# ardBeeQueenWMountHoles50x52.net
KiCad netlist of a schematic drawn in EAGLE
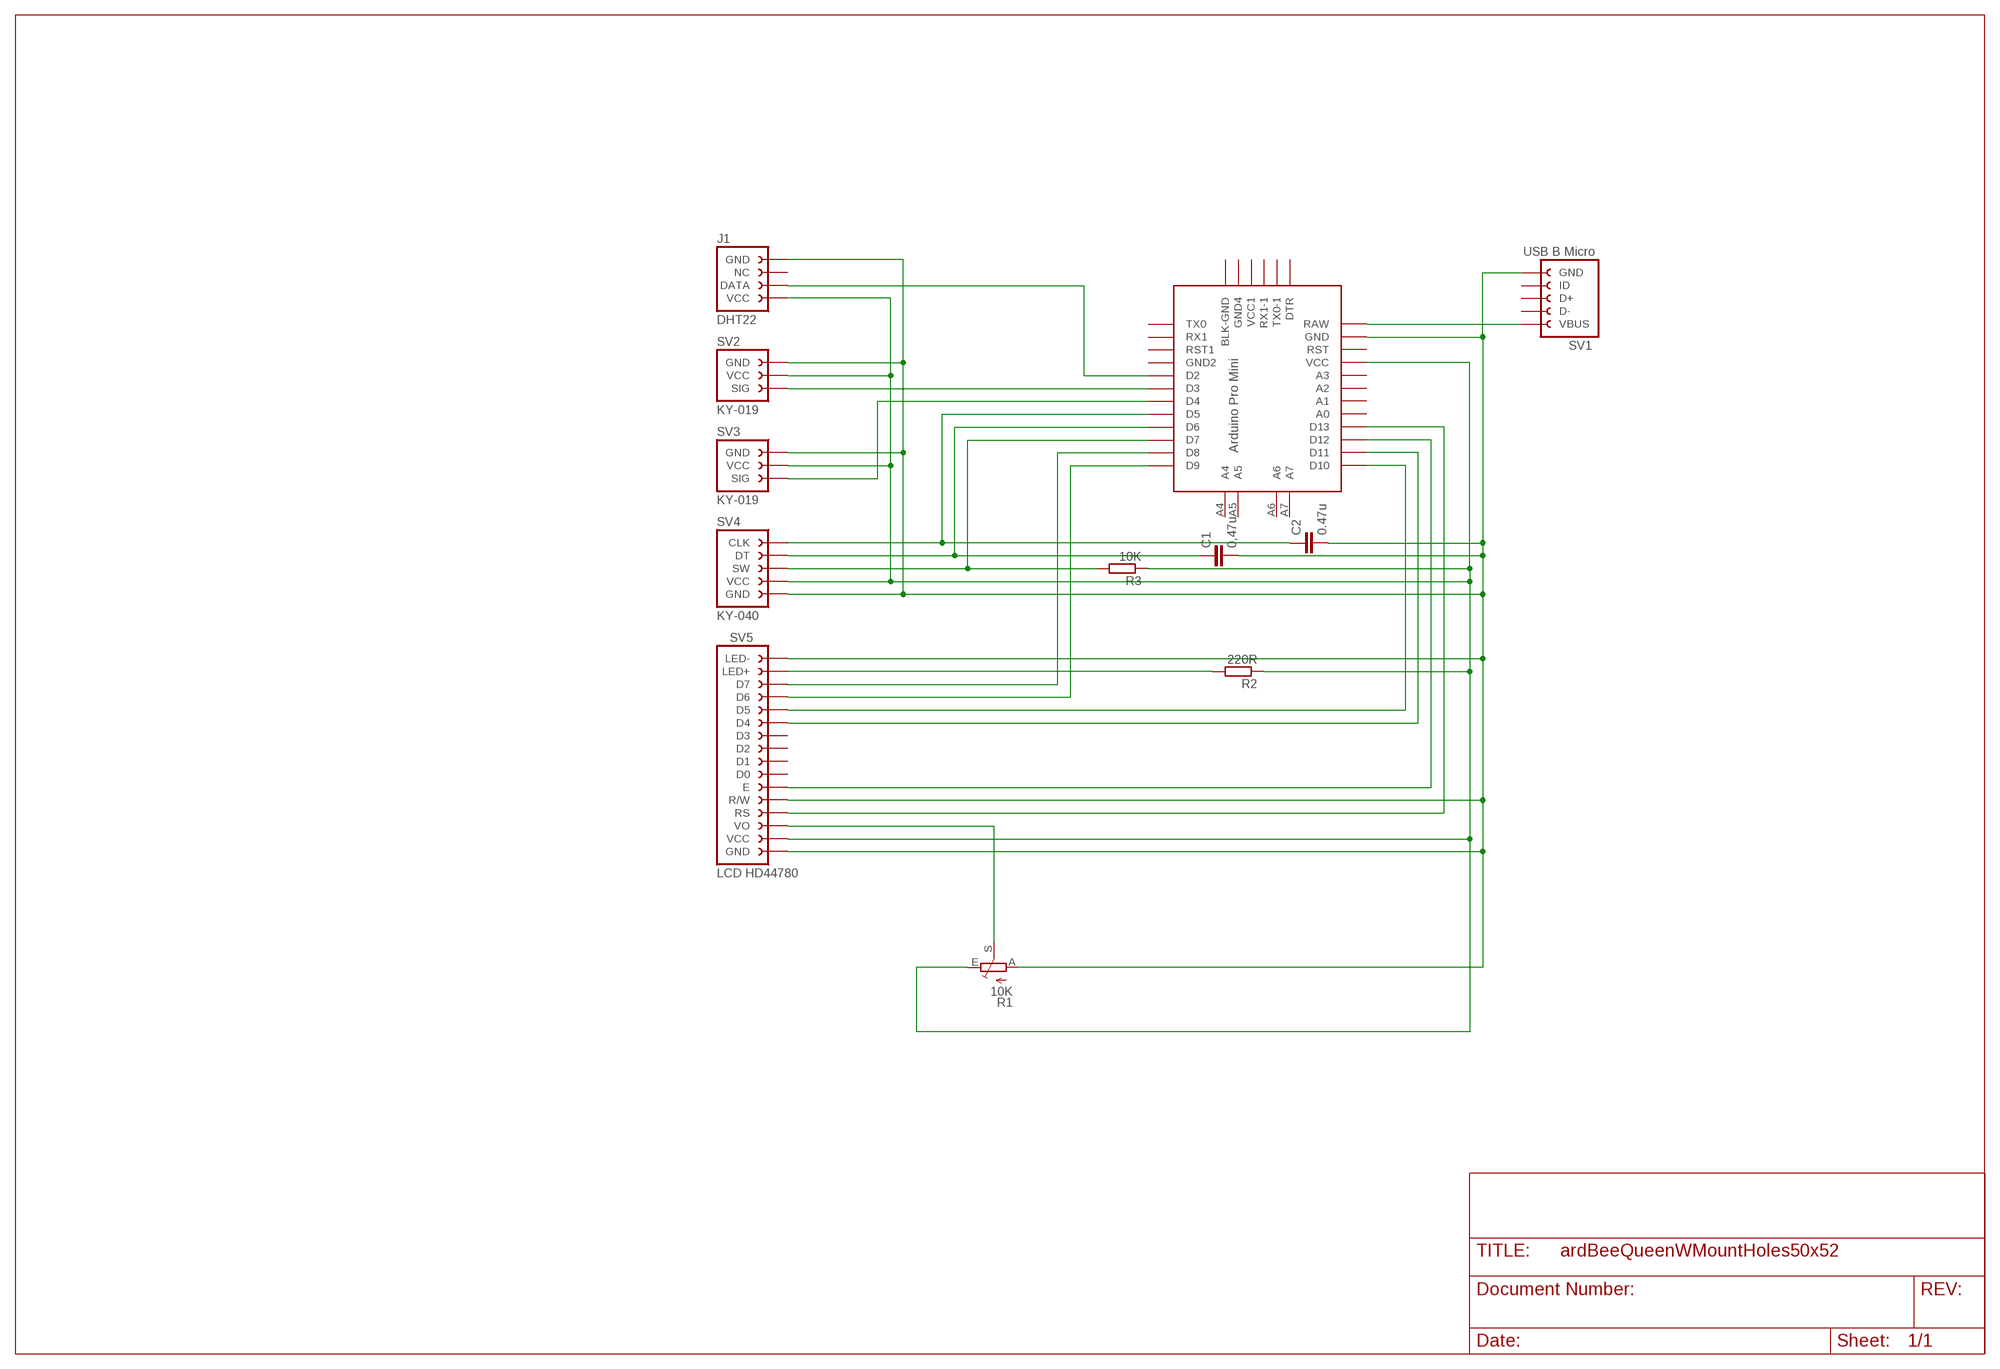
[diagram p0: schematic, sheet 1]

(export (version "E")
  (design (tool "Eeschema 10.0.6"))
  (components
    (comp (ref "C1")
      (value "0,47u")
      (footprint "eagle-import:C050-024X044")
      (libsource (lib "eagle-import") (part "C-EU050-024X044"))
    )
    (comp (ref "C2")
      (value "0.47u")
      (footprint "eagle-import:C050-024X044")
      (libsource (lib "eagle-import") (part "C-EU050-024X044"))
    )
    (comp (ref "J1")
      (value "DHT22_4-PIN_FEMALE_HEADERPTH")
      (footprint "eagle-import:DHT22_4-PIN_FEMALE_HEADER")
      (libsource (lib "eagle-import") (part "DHT22_4-PIN_FEMALE_HEADERPTH"))
    )
    (comp (ref "R1")
      (value "10K")
      (footprint "eagle-import:B25P")
      (libsource (lib "eagle-import") (part "TRIM_EU-B25P"))
    )
    (comp (ref "R2")
      (value "220R")
      (footprint "eagle-import:0207_10")
      (libsource (lib "eagle-import") (part "R-EU_0207/10"))
    )
    (comp (ref "R3")
      (value "10K")
      (footprint "eagle-import:0207_10")
      (libsource (lib "eagle-import") (part "R-EU_0207/10"))
    )
    (comp (ref "SV1")
      (value "MICROUSB_B_BREAKOUT_5-PIN_FEMALE_HEADERWITH_MOUNT_HOLES")
      (footprint "eagle-import:MICROUSB_B_BREAKOUT_5-PIN_FEMALE_HEADER_W_MOUNT_HOLES")
      (libsource (lib "eagle-import") (part "MICROUSB_B_BREAKOUT_5-PIN_FEMALE_HEADERWITH_MOUNT_HOLES"))
    )
    (comp (ref "SV2")
      (value "KY-019_3-PIN_FEMALE_HEADER")
      (footprint "eagle-import:KY-019_3-PIN_FEMALE_HEADER")
      (libsource (lib "eagle-import") (part "KY-019_3-PIN_FEMALE_HEADER"))
    )
    (comp (ref "SV3")
      (value "KY-019_3-PIN_FEMALE_HEADER")
      (footprint "eagle-import:KY-019_3-PIN_FEMALE_HEADER")
      (libsource (lib "eagle-import") (part "KY-019_3-PIN_FEMALE_HEADER"))
    )
    (comp (ref "SV4")
      (value "KY-040_5-PIN_FEMALE_HEADER")
      (footprint "eagle-import:KY-040_5-PIN_FEMALE_HEADER")
      (libsource (lib "eagle-import") (part "KY-040_5-PIN_FEMALE_HEADER"))
    )
    (comp (ref "SV5")
      (value "LCD-HD44780-16-PIN_FEMALE_HEADER")
      (footprint "eagle-import:LCD-HD44780-16-PIN_FEMALE_HEADER")
      (libsource (lib "eagle-import") (part "LCD-HD44780-16-PIN_FEMALE_HEADER"))
    )
    (comp (ref "U$1")
      (value "ARDUINO_PRO_MINI-2")
      (footprint "eagle-import:ARDUINO_PRO_MINI-2")
      (libsource (lib "eagle-import") (part "ARDUINO_PRO_MINI-2"))
    )
  )
  (nets
    (net (code "1") (name "Net-(C1-Pad1)") (class "Default")
      (node (ref "C1") (pin "1") (pinfunction "1_1") (pintype "passive"))
      (node (ref "SV4") (pin "DT") (pinfunction "DT_DT") (pintype "passive"))
      (node (ref "U$1") (pin "D6") (pinfunction "D6_D6") (pintype "bidirectional"))
    )
    (net (code "2") (name "Net-(C1-Pad2)") (class "Default")
      (node (ref "C1") (pin "2") (pinfunction "2_2") (pintype "passive"))
      (node (ref "C2") (pin "2") (pinfunction "2_2") (pintype "passive"))
      (node (ref "J1") (pin "GND") (pinfunction "GND_GND") (pintype "passive"))
      (node (ref "R1") (pin "A") (pinfunction "A_A") (pintype "passive"))
      (node (ref "SV1") (pin "GND") (pinfunction "GND_GND") (pintype "passive"))
      (node (ref "SV2") (pin "GND") (pinfunction "GND_GND") (pintype "passive"))
      (node (ref "SV3") (pin "GND") (pinfunction "GND_GND") (pintype "passive"))
      (node (ref "SV4") (pin "GND") (pinfunction "GND_GND") (pintype "passive"))
      (node (ref "SV5") (pin "GND") (pinfunction "GND_GND") (pintype "passive"))
      (node (ref "SV5") (pin "LED-") (pinfunction "LED-_LED-") (pintype "passive"))
      (node (ref "SV5") (pin "R/W") (pinfunction "R/W_R/W") (pintype "passive"))
      (node (ref "U$1") (pin "GND") (pinfunction "GND_GND") (pintype "bidirectional"))
    )
    (net (code "3") (name "Net-(C2-Pad1)") (class "Default")
      (node (ref "C2") (pin "1") (pinfunction "1_1") (pintype "passive"))
      (node (ref "SV4") (pin "CLK") (pinfunction "CLK_CLK") (pintype "passive"))
      (node (ref "U$1") (pin "D5") (pinfunction "D5_D5") (pintype "bidirectional"))
    )
    (net (code "4") (name "Net-(J1-PadDATA)") (class "Default")
      (node (ref "J1") (pin "DATA") (pinfunction "DATA_DATA") (pintype "passive"))
      (node (ref "U$1") (pin "D2") (pinfunction "D2_D2") (pintype "bidirectional"))
    )
    (net (code "5") (name "Net-(J1-PadVCC)") (class "Default")
      (node (ref "J1") (pin "VCC") (pinfunction "VCC_VCC") (pintype "passive"))
      (node (ref "R1") (pin "E") (pinfunction "E_E") (pintype "passive"))
      (node (ref "R2") (pin "1") (pinfunction "1_1") (pintype "passive"))
      (node (ref "R3") (pin "1") (pinfunction "1_1") (pintype "passive"))
      (node (ref "SV2") (pin "VCC") (pinfunction "VCC_VCC") (pintype "passive"))
      (node (ref "SV3") (pin "VCC") (pinfunction "VCC_VCC") (pintype "passive"))
      (node (ref "SV4") (pin "VCC") (pinfunction "VCC_VCC") (pintype "passive"))
      (node (ref "SV5") (pin "VCC") (pinfunction "VCC_VCC") (pintype "passive"))
      (node (ref "U$1") (pin "VCC") (pinfunction "VCC_VCC") (pintype "bidirectional"))
    )
    (net (code "6") (name "Net-(R1-PadS)") (class "Default")
      (node (ref "R1") (pin "S") (pinfunction "S_S") (pintype "passive"))
      (node (ref "SV5") (pin "VO") (pinfunction "VO_VO") (pintype "passive"))
    )
    (net (code "7") (name "Net-(R2-Pad2)") (class "Default")
      (node (ref "R2") (pin "2") (pinfunction "2_2") (pintype "passive"))
      (node (ref "SV5") (pin "LED+") (pinfunction "LED+_LED+") (pintype "passive"))
    )
    (net (code "8") (name "Net-(R3-Pad2)") (class "Default")
      (node (ref "R3") (pin "2") (pinfunction "2_2") (pintype "passive"))
      (node (ref "SV4") (pin "SW") (pinfunction "SW_SW") (pintype "passive"))
      (node (ref "U$1") (pin "D7") (pinfunction "D7_D7") (pintype "bidirectional"))
    )
    (net (code "9") (name "Net-(SV1-PadVBUS)") (class "Default")
      (node (ref "SV1") (pin "VBUS") (pinfunction "VBUS_VBUS") (pintype "passive"))
      (node (ref "U$1") (pin "RAW") (pinfunction "RAW_RAW") (pintype "bidirectional"))
    )
    (net (code "10") (name "Net-(SV2-PadSIG)") (class "Default")
      (node (ref "SV2") (pin "SIG") (pinfunction "SIG_SIG") (pintype "passive"))
      (node (ref "U$1") (pin "D3") (pinfunction "D3_D3") (pintype "bidirectional"))
    )
    (net (code "11") (name "Net-(SV3-PadSIG)") (class "Default")
      (node (ref "SV3") (pin "SIG") (pinfunction "SIG_SIG") (pintype "passive"))
      (node (ref "U$1") (pin "D4") (pinfunction "D4_D4") (pintype "bidirectional"))
    )
    (net (code "12") (name "Net-(SV5-PadD4)") (class "Default")
      (node (ref "SV5") (pin "D4") (pinfunction "D4_D4") (pintype "passive"))
      (node (ref "U$1") (pin "D11") (pinfunction "D11_D11") (pintype "bidirectional"))
    )
    (net (code "13") (name "Net-(SV5-PadD5)") (class "Default")
      (node (ref "SV5") (pin "D5") (pinfunction "D5_D5") (pintype "passive"))
      (node (ref "U$1") (pin "D10") (pinfunction "D10_D10") (pintype "bidirectional"))
    )
    (net (code "14") (name "Net-(SV5-PadD6)") (class "Default")
      (node (ref "SV5") (pin "D6") (pinfunction "D6_D6") (pintype "passive"))
      (node (ref "U$1") (pin "D9") (pinfunction "D9_D9") (pintype "bidirectional"))
    )
    (net (code "15") (name "Net-(SV5-PadD7)") (class "Default")
      (node (ref "SV5") (pin "D7") (pinfunction "D7_D7") (pintype "passive"))
      (node (ref "U$1") (pin "D8") (pinfunction "D8_D8") (pintype "bidirectional"))
    )
    (net (code "16") (name "Net-(SV5-PadE)") (class "Default")
      (node (ref "SV5") (pin "E") (pinfunction "E_E") (pintype "passive"))
      (node (ref "U$1") (pin "D12") (pinfunction "D12_D12") (pintype "bidirectional"))
    )
    (net (code "17") (name "Net-(SV5-PadRS)") (class "Default")
      (node (ref "SV5") (pin "RS") (pinfunction "RS_RS") (pintype "passive"))
      (node (ref "U$1") (pin "D13") (pinfunction "D13_D13") (pintype "bidirectional"))
    )
    (net (code "18") (name "unconnected-(J1-PadNC)") (class "Default")
      (node (ref "J1") (pin "NC") (pinfunction "NC_NC") (pintype "passive"))
    )
    (net (code "19") (name "unconnected-(SV1-PadD+)") (class "Default")
      (node (ref "SV1") (pin "D+") (pinfunction "D+_D+") (pintype "passive"))
    )
    (net (code "20") (name "unconnected-(SV1-PadD-)") (class "Default")
      (node (ref "SV1") (pin "D-") (pinfunction "D-_D-") (pintype "passive"))
    )
    (net (code "21") (name "unconnected-(SV1-PadID)") (class "Default")
      (node (ref "SV1") (pin "ID") (pinfunction "ID_ID") (pintype "passive"))
    )
    (net (code "22") (name "unconnected-(SV5-PadD0)") (class "Default")
      (node (ref "SV5") (pin "D0") (pinfunction "D0_D0") (pintype "passive"))
    )
    (net (code "23") (name "unconnected-(SV5-PadD1)") (class "Default")
      (node (ref "SV5") (pin "D1") (pinfunction "D1_D1") (pintype "passive"))
    )
    (net (code "24") (name "unconnected-(SV5-PadD2)") (class "Default")
      (node (ref "SV5") (pin "D2") (pinfunction "D2_D2") (pintype "passive"))
    )
    (net (code "25") (name "unconnected-(SV5-PadD3)") (class "Default")
      (node (ref "SV5") (pin "D3") (pinfunction "D3_D3") (pintype "passive"))
    )
    (net (code "26") (name "unconnected-(U$1-GND2-PadGND1)") (class "Default")
      (node (ref "U$1") (pin "GND1") (pinfunction "GND2_GND1") (pintype "bidirectional"))
    )
    (net (code "27") (name "unconnected-(U$1-GND4-PadGND3)") (class "Default")
      (node (ref "U$1") (pin "GND3") (pinfunction "GND4_GND3") (pintype "bidirectional"))
    )
    (net (code "28") (name "unconnected-(U$1-PadA0)") (class "Default")
      (node (ref "U$1") (pin "A0") (pinfunction "A0_A0") (pintype "bidirectional"))
    )
    (net (code "29") (name "unconnected-(U$1-PadA1)") (class "Default")
      (node (ref "U$1") (pin "A1") (pinfunction "A1_A1") (pintype "bidirectional"))
    )
    (net (code "30") (name "unconnected-(U$1-PadA2)") (class "Default")
      (node (ref "U$1") (pin "A2") (pinfunction "A2_A2") (pintype "bidirectional"))
    )
    (net (code "31") (name "unconnected-(U$1-PadA3)") (class "Default")
      (node (ref "U$1") (pin "A3") (pinfunction "A3_A3") (pintype "bidirectional"))
    )
    (net (code "32") (name "unconnected-(U$1-PadA4)") (class "Default")
      (node (ref "U$1") (pin "A4") (pinfunction "A4_A4") (pintype "bidirectional"))
    )
    (net (code "33") (name "unconnected-(U$1-PadA5)") (class "Default")
      (node (ref "U$1") (pin "A5") (pinfunction "A5_A5") (pintype "bidirectional"))
    )
    (net (code "34") (name "unconnected-(U$1-PadA6)") (class "Default")
      (node (ref "U$1") (pin "A6") (pinfunction "A6_A6") (pintype "bidirectional"))
    )
    (net (code "35") (name "unconnected-(U$1-PadA7)") (class "Default")
      (node (ref "U$1") (pin "A7") (pinfunction "A7_A7") (pintype "bidirectional"))
    )
    (net (code "36") (name "unconnected-(U$1-PadBLK-GND)") (class "Default")
      (node (ref "U$1") (pin "BLK-GND") (pinfunction "BLK-GND_BLK-GND") (pintype "bidirectional"))
    )
    (net (code "37") (name "unconnected-(U$1-PadDTR)") (class "Default")
      (node (ref "U$1") (pin "DTR") (pinfunction "DTR_DTR") (pintype "bidirectional"))
    )
    (net (code "38") (name "unconnected-(U$1-PadRST)") (class "Default")
      (node (ref "U$1") (pin "RST") (pinfunction "RST_RST") (pintype "bidirectional"))
    )
    (net (code "39") (name "unconnected-(U$1-PadRST1)") (class "Default")
      (node (ref "U$1") (pin "RST1") (pinfunction "RST1_RST1") (pintype "bidirectional"))
    )
    (net (code "40") (name "unconnected-(U$1-PadRX1)") (class "Default")
      (node (ref "U$1") (pin "RX1") (pinfunction "RX1_RX1") (pintype "bidirectional"))
    )
    (net (code "41") (name "unconnected-(U$1-PadRX1-1)") (class "Default")
      (node (ref "U$1") (pin "RX1-1") (pinfunction "RX1-1_RX1-1") (pintype "bidirectional"))
    )
    (net (code "42") (name "unconnected-(U$1-PadTX0)") (class "Default")
      (node (ref "U$1") (pin "TX0") (pinfunction "TX0_TX0") (pintype "bidirectional"))
    )
    (net (code "43") (name "unconnected-(U$1-PadTX0-1)") (class "Default")
      (node (ref "U$1") (pin "TX0-1") (pinfunction "TX0-1_TX0-1") (pintype "bidirectional"))
    )
    (net (code "44") (name "unconnected-(U$1-PadVCC1)") (class "Default")
      (node (ref "U$1") (pin "VCC1") (pinfunction "VCC1_VCC1") (pintype "bidirectional"))
    )
  )
)
